# Qwiic_TMF8801.net
KiCad netlist of a schematic drawn in EAGLE
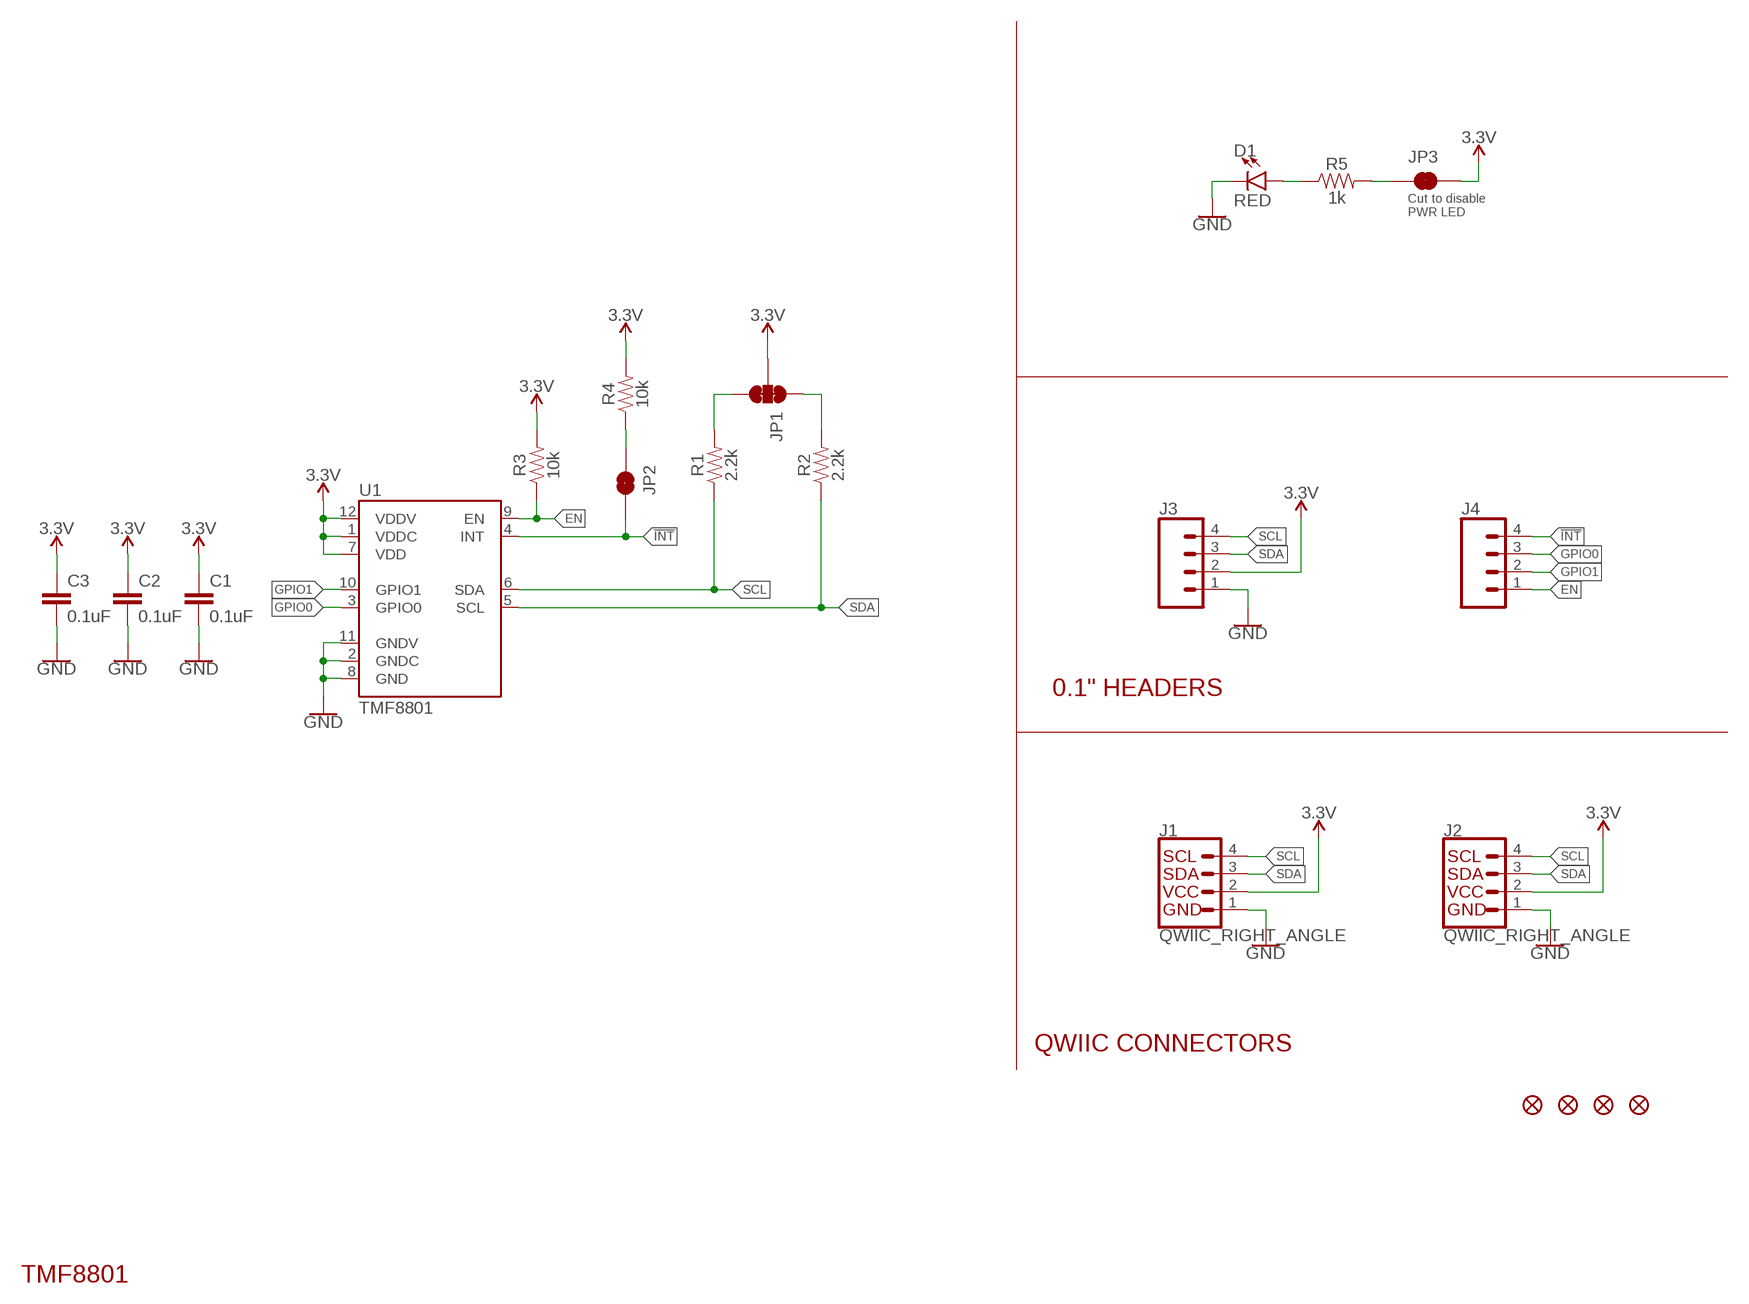
[diagram p0: schematic, sheet 1]

(export (version "E")
  (design (tool "Eeschema 10.0.6"))
  (components
    (comp (ref "C1")
      (value "0.1uF")
      (footprint "eagle-import:0603")
      (libsource (lib "eagle-import") (part "0.1UF-0603-25V-(+80/-20%)"))
    )
    (comp (ref "C2")
      (value "0.1uF")
      (footprint "eagle-import:0603")
      (libsource (lib "eagle-import") (part "0.1UF-0603-25V-(+80/-20%)"))
    )
    (comp (ref "C3")
      (value "0.1uF")
      (footprint "eagle-import:0603")
      (libsource (lib "eagle-import") (part "0.1UF-0603-25V-(+80/-20%)"))
    )
    (comp (ref "D1")
      (value "RED")
      (footprint "eagle-import:LED-0603")
      (libsource (lib "eagle-import") (part "LED-RED0603"))
    )
    (comp (ref "FD1")
      (value "FIDUCIAL1X2")
      (footprint "eagle-import:FIDUCIAL-1X2")
      (libsource (lib "eagle-import") (part "FIDUCIAL1X2"))
    )
    (comp (ref "FD2")
      (value "FIDUCIAL1X2")
      (footprint "eagle-import:FIDUCIAL-1X2")
      (libsource (lib "eagle-import") (part "FIDUCIAL1X2"))
    )
    (comp (ref "FD3")
      (value "FIDUCIAL1X2")
      (footprint "eagle-import:FIDUCIAL-1X2")
      (libsource (lib "eagle-import") (part "FIDUCIAL1X2"))
    )
    (comp (ref "FD4")
      (value "FIDUCIAL1X2")
      (footprint "eagle-import:FIDUCIAL-1X2")
      (libsource (lib "eagle-import") (part "FIDUCIAL1X2"))
    )
    (comp (ref "J1")
      (value "QWIIC_RIGHT_ANGLE")
      (footprint "eagle-import:JST04_1MM_RA")
      (libsource (lib "eagle-import") (part "QWIIC_CONNECTORJS-1MM"))
    )
    (comp (ref "J2")
      (value "QWIIC_RIGHT_ANGLE")
      (footprint "eagle-import:JST04_1MM_RA")
      (libsource (lib "eagle-import") (part "QWIIC_CONNECTORJS-1MM"))
    )
    (comp (ref "J3")
      (value "CONN_041X04_NO_SILK")
      (footprint "eagle-import:1X04_NO_SILK")
      (libsource (lib "eagle-import") (part "CONN_041X04_NO_SILK"))
    )
    (comp (ref "J4")
      (value "CONN_041X04_NO_SILK")
      (footprint "eagle-import:1X04_NO_SILK")
      (libsource (lib "eagle-import") (part "CONN_041X04_NO_SILK"))
    )
    (comp (ref "JP1")
      (value "JUMPER-SMT_3_2-NC_TRACE_SILK")
      (footprint "eagle-import:SMT-JUMPER_3_2-NC_TRACE_SILK")
      (libsource (lib "eagle-import") (part "JUMPER-SMT_3_2-NC_TRACE_SILK"))
    )
    (comp (ref "JP2")
      (value "JUMPER-SMT_2_NC_TRACE_SILK")
      (footprint "eagle-import:SMT-JUMPER_2_NC_TRACE_SILK")
      (libsource (lib "eagle-import") (part "JUMPER-SMT_2_NC_TRACE_SILK"))
    )
    (comp (ref "JP3")
      (value "JUMPER-SMT_2_NC_TRACE_SILK")
      (footprint "eagle-import:SMT-JUMPER_2_NC_TRACE_SILK")
      (libsource (lib "eagle-import") (part "JUMPER-SMT_2_NC_TRACE_SILK"))
    )
    (comp (ref "R1")
      (value "2.2k")
      (footprint "eagle-import:0603")
      (libsource (lib "eagle-import") (part "2.2KOHM-0603-1/10W-1%"))
    )
    (comp (ref "R2")
      (value "2.2k")
      (footprint "eagle-import:0603")
      (libsource (lib "eagle-import") (part "2.2KOHM-0603-1/10W-1%"))
    )
    (comp (ref "R3")
      (value "10k")
      (footprint "eagle-import:0603")
      (libsource (lib "eagle-import") (part "10KOHM-0603-1/10W-1%"))
    )
    (comp (ref "R4")
      (value "10k")
      (footprint "eagle-import:0603")
      (libsource (lib "eagle-import") (part "10KOHM-0603-1/10W-1%"))
    )
    (comp (ref "R5")
      (value "1k")
      (footprint "eagle-import:0603")
      (libsource (lib "eagle-import") (part "1KOHM-0603-1/10W-1%"))
    )
    (comp (ref "U1")
      (value "TMF8801")
      (footprint "eagle-import:TMF8801-CUSTOM")
      (libsource (lib "eagle-import") (part "TMF8801TMF8801"))
    )
  )
  (nets
    (net (code "1") (name "/~{INT}") (class "Default")
      (node (ref "J4") (pin "4") (pinfunction "4_4") (pintype "passive"))
      (node (ref "JP2") (pin "2") (pinfunction "2_2") (pintype "passive"))
      (node (ref "U1") (pin "4") (pinfunction "INT_4") (pintype "open_collector"))
    )
    (net (code "2") (name "3.3V") (class "Default")
      (node (ref "C1") (pin "1") (pinfunction "1_1") (pintype "passive"))
      (node (ref "C2") (pin "1") (pinfunction "1_1") (pintype "passive"))
      (node (ref "C3") (pin "1") (pinfunction "1_1") (pintype "passive"))
      (node (ref "J1") (pin "2") (pinfunction "2_2") (pintype "power_in"))
      (node (ref "J2") (pin "2") (pinfunction "2_2") (pintype "power_in"))
      (node (ref "J3") (pin "2") (pinfunction "2_2") (pintype "passive"))
      (node (ref "JP1") (pin "2") (pinfunction "2_2") (pintype "passive"))
      (node (ref "JP3") (pin "2") (pinfunction "2_2") (pintype "passive"))
      (node (ref "R3") (pin "2") (pinfunction "2_2") (pintype "passive"))
      (node (ref "R4") (pin "2") (pinfunction "2_2") (pintype "passive"))
      (node (ref "U1") (pin "1") (pinfunction "VDDC_1") (pintype "power_in"))
      (node (ref "U1") (pin "12") (pinfunction "VDDV_12") (pintype "power_in"))
      (node (ref "U1") (pin "7") (pinfunction "VDD_7") (pintype "power_in"))
    )
    (net (code "3") (name "EN") (class "Default")
      (node (ref "J4") (pin "1") (pinfunction "1_1") (pintype "passive"))
      (node (ref "R3") (pin "1") (pinfunction "1_1") (pintype "passive"))
      (node (ref "U1") (pin "9") (pinfunction "EN_9") (pintype "input"))
    )
    (net (code "4") (name "GND") (class "Default")
      (node (ref "C1") (pin "2") (pinfunction "2_2") (pintype "passive"))
      (node (ref "C2") (pin "2") (pinfunction "2_2") (pintype "passive"))
      (node (ref "C3") (pin "2") (pinfunction "2_2") (pintype "passive"))
      (node (ref "D1") (pin "C") (pinfunction "C_C") (pintype "passive"))
      (node (ref "J1") (pin "1") (pinfunction "1_1") (pintype "power_in"))
      (node (ref "J2") (pin "1") (pinfunction "1_1") (pintype "power_in"))
      (node (ref "J3") (pin "1") (pinfunction "1_1") (pintype "passive"))
      (node (ref "U1") (pin "11") (pinfunction "GNDV_11") (pintype "power_in"))
      (node (ref "U1") (pin "2") (pinfunction "GNDC_2") (pintype "power_in"))
      (node (ref "U1") (pin "8") (pinfunction "GND_8") (pintype "power_in"))
    )
    (net (code "5") (name "GPIO0") (class "Default")
      (node (ref "J4") (pin "3") (pinfunction "3_3") (pintype "passive"))
      (node (ref "U1") (pin "3") (pinfunction "GPIO0_3") (pintype "bidirectional"))
    )
    (net (code "6") (name "GPIO1") (class "Default")
      (node (ref "J4") (pin "2") (pinfunction "2_2") (pintype "passive"))
      (node (ref "U1") (pin "10") (pinfunction "GPIO1_10") (pintype "bidirectional"))
    )
    (net (code "7") (name "Net-(D1-PadA)") (class "Default")
      (node (ref "D1") (pin "A") (pinfunction "A_A") (pintype "passive"))
      (node (ref "R5") (pin "1") (pinfunction "1_1") (pintype "passive"))
    )
    (net (code "8") (name "Net-(JP1-Pad1)") (class "Default")
      (node (ref "JP1") (pin "1") (pinfunction "1_1") (pintype "passive"))
      (node (ref "R2") (pin "2") (pinfunction "2_2") (pintype "passive"))
    )
    (net (code "9") (name "Net-(JP1-Pad3)") (class "Default")
      (node (ref "JP1") (pin "3") (pinfunction "3_3") (pintype "passive"))
      (node (ref "R1") (pin "2") (pinfunction "2_2") (pintype "passive"))
    )
    (net (code "10") (name "Net-(JP2-Pad1)") (class "Default")
      (node (ref "JP2") (pin "1") (pinfunction "1_1") (pintype "passive"))
      (node (ref "R4") (pin "1") (pinfunction "1_1") (pintype "passive"))
    )
    (net (code "11") (name "Net-(JP3-Pad1)") (class "Default")
      (node (ref "JP3") (pin "1") (pinfunction "1_1") (pintype "passive"))
      (node (ref "R5") (pin "2") (pinfunction "2_2") (pintype "passive"))
    )
    (net (code "12") (name "SCL") (class "Default")
      (node (ref "J1") (pin "4") (pinfunction "4_4") (pintype "passive"))
      (node (ref "J2") (pin "4") (pinfunction "4_4") (pintype "passive"))
      (node (ref "J3") (pin "4") (pinfunction "4_4") (pintype "passive"))
      (node (ref "R1") (pin "1") (pinfunction "1_1") (pintype "passive"))
      (node (ref "U1") (pin "6") (pinfunction "SDA_6") (pintype "bidirectional"))
    )
    (net (code "13") (name "SDA") (class "Default")
      (node (ref "J1") (pin "3") (pinfunction "3_3") (pintype "passive"))
      (node (ref "J2") (pin "3") (pinfunction "3_3") (pintype "passive"))
      (node (ref "J3") (pin "3") (pinfunction "3_3") (pintype "passive"))
      (node (ref "R2") (pin "1") (pinfunction "1_1") (pintype "passive"))
      (node (ref "U1") (pin "5") (pinfunction "SCL_5") (pintype "bidirectional"))
    )
  )
)
